# tick-mk-4_5.net
KiCad netlist of a schematic drawn in EAGLE
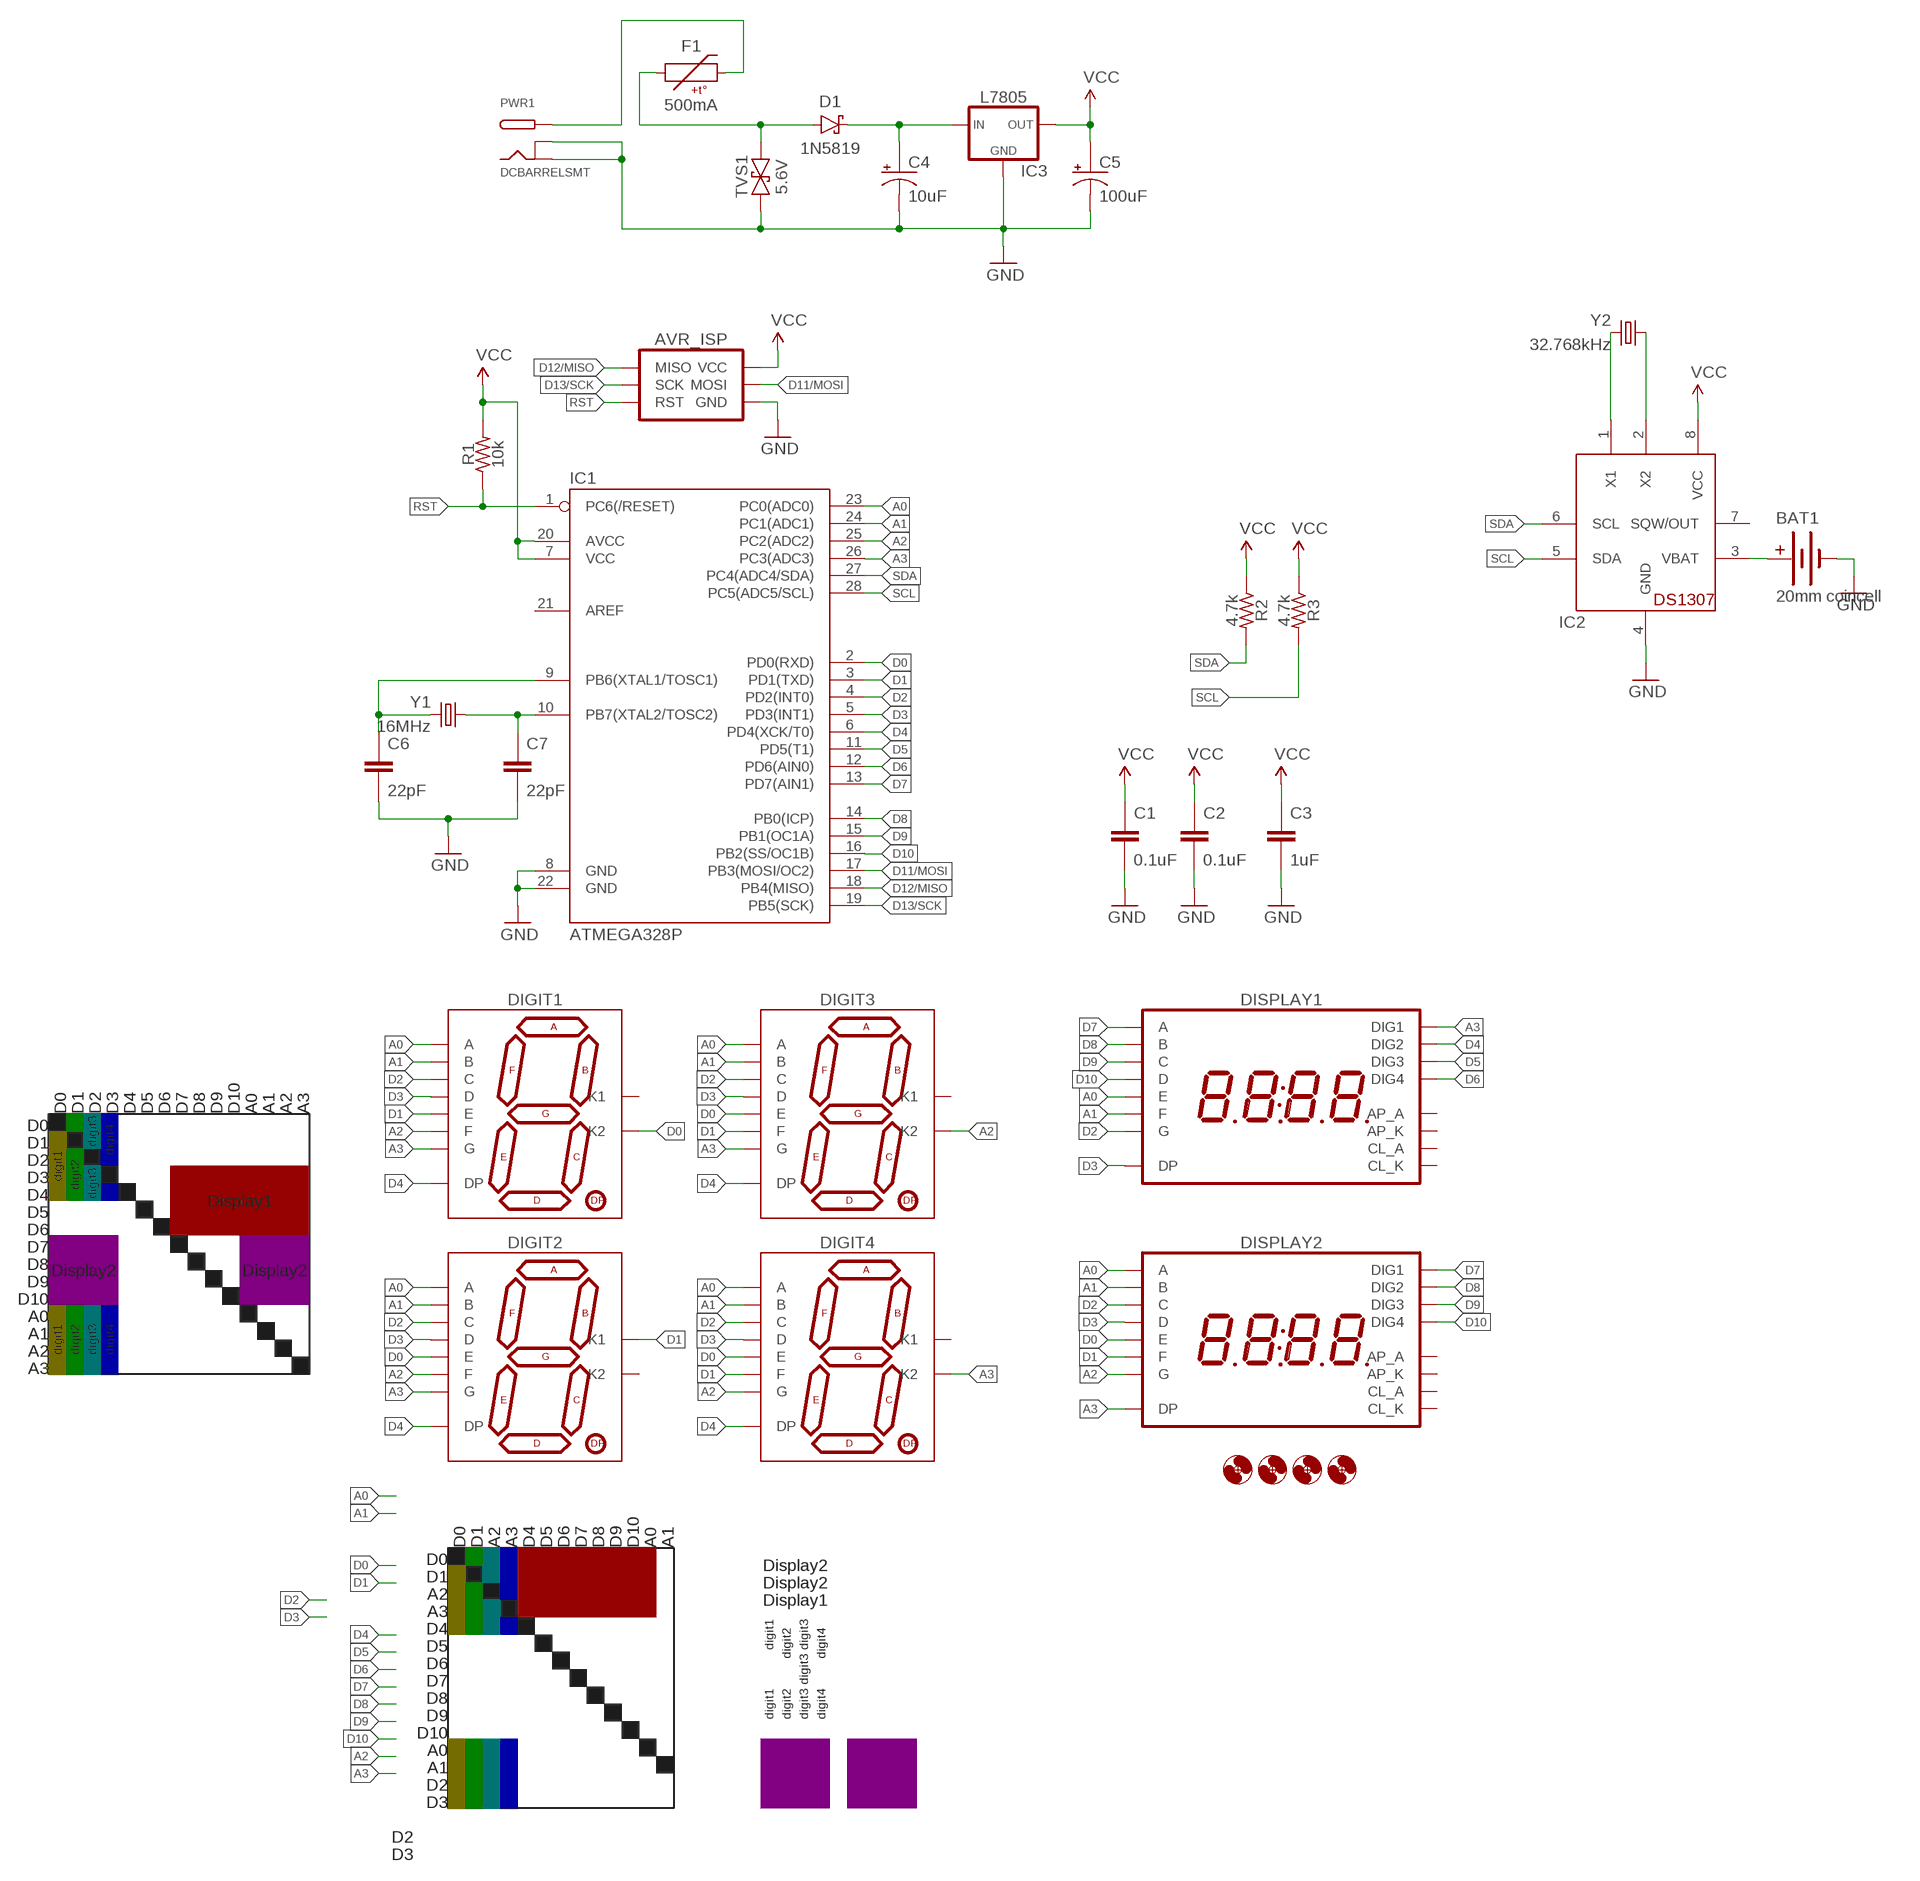
[diagram p0: schematic, sheet 1]

(export (version "E")
  (design (tool "Eeschema 10.0.6"))
  (components
    (comp (ref "AVR_ISP")
      (value "AVR_SPI_PRG_6PTH")
      (footprint "eagle-import:2X3")
      (libsource (lib "eagle-import") (part "AVR_SPI_PRG_6PTH"))
    )
    (comp (ref "BAT1")
      (value "20mm coincell")
      (footprint "eagle-import:BATTCON_20MM_MINE")
      (libsource (lib "eagle-import") (part "BATTERY20MMSMD-MINE"))
    )
    (comp (ref "C1")
      (value "0.1uF")
      (footprint "eagle-import:C025-024X044")
      (libsource (lib "eagle-import") (part "CAPACITOR-CERAMIC025-024X044"))
    )
    (comp (ref "C2")
      (value "0.1uF")
      (footprint "eagle-import:C025-024X044")
      (libsource (lib "eagle-import") (part "CAPACITOR-CERAMIC025-024X044"))
    )
    (comp (ref "C3")
      (value "1uF")
      (footprint "eagle-import:C025-024X044")
      (libsource (lib "eagle-import") (part "CAPACITOR-CERAMIC025-024X044"))
    )
    (comp (ref "C4")
      (value "10uF")
      (footprint "eagle-import:E2-5")
      (libsource (lib "eagle-import") (part "CAPACITOR-POLARIZEDE2-5"))
    )
    (comp (ref "C5")
      (value "100uF")
      (footprint "eagle-import:E2,5-6")
      (libsource (lib "eagle-import") (part "CAPACITOR-POLARIZEDE2.5-6"))
    )
    (comp (ref "C6")
      (value "22pF")
      (footprint "eagle-import:C025-024X044")
      (libsource (lib "eagle-import") (part "CAPACITOR-CERAMIC025-024X044"))
    )
    (comp (ref "C7")
      (value "22pF")
      (footprint "eagle-import:C025-024X044")
      (libsource (lib "eagle-import") (part "CAPACITOR-CERAMIC025-024X044"))
    )
    (comp (ref "D1")
      (value "1N5819")
      (footprint "eagle-import:DIODE-10.16MM")
      (libsource (lib "eagle-import") (part "DIODE-SCHOTTKYPTH-10.16MM"))
    )
    (comp (ref "DIGIT1")
      (value "7SEG_1DIGPTH-25.4MM-BARE")
      (footprint "eagle-import:7SEG_1DIG_25.4MM_NOSILK")
      (libsource (lib "eagle-import") (part "7SEG_1DIGPTH-25.4MM-BARE"))
    )
    (comp (ref "DIGIT2")
      (value "7SEG_1DIGPTH-25.4MM-BARE")
      (footprint "eagle-import:7SEG_1DIG_25.4MM_NOSILK")
      (libsource (lib "eagle-import") (part "7SEG_1DIGPTH-25.4MM-BARE"))
    )
    (comp (ref "DIGIT3")
      (value "7SEG_1DIGPTH-25.4MM-BARE")
      (footprint "eagle-import:7SEG_1DIG_25.4MM_NOSILK")
      (libsource (lib "eagle-import") (part "7SEG_1DIGPTH-25.4MM-BARE"))
    )
    (comp (ref "DIGIT4")
      (value "7SEG_1DIGPTH-25.4MM-BARE")
      (footprint "eagle-import:7SEG_1DIG_25.4MM_NOSILK")
      (libsource (lib "eagle-import") (part "7SEG_1DIGPTH-25.4MM-BARE"))
    )
    (comp (ref "DISPLAY1")
      (value "7SEG_4DIGIT_COLON_APOS")
      (footprint "eagle-import:7SEG_4DIG_10MM")
      (libsource (lib "eagle-import") (part "7SEG_4DIGIT_COLON_APOS"))
    )
    (comp (ref "DISPLAY2")
      (value "7SEG_4DIGIT_COLON_APOS")
      (footprint "eagle-import:7SEG_4DIG_10MM")
      (libsource (lib "eagle-import") (part "7SEG_4DIGIT_COLON_APOS"))
    )
    (comp (ref "F1")
      (value "500mA")
      (footprint "eagle-import:PTC-PTH-5.08MM")
      (libsource (lib "eagle-import") (part "PTCPTH-5.08MM"))
    )
    (comp (ref "H1")
      (value "HOLE#2")
      (footprint "eagle-import:HOLE-#2")
      (libsource (lib "eagle-import") (part "HOLE#2"))
    )
    (comp (ref "H2")
      (value "HOLE#2")
      (footprint "eagle-import:HOLE-#2")
      (libsource (lib "eagle-import") (part "HOLE#2"))
    )
    (comp (ref "H3")
      (value "HOLE#2")
      (footprint "eagle-import:HOLE-#2")
      (libsource (lib "eagle-import") (part "HOLE#2"))
    )
    (comp (ref "H4")
      (value "HOLE#2")
      (footprint "eagle-import:HOLE-#2")
      (libsource (lib "eagle-import") (part "HOLE#2"))
    )
    (comp (ref "IC1")
      (value "ATMEGA328P")
      (footprint "eagle-import:DIL28-3")
      (libsource (lib "eagle-import") (part "ATMEGA328P_PDIP"))
    )
    (comp (ref "IC2")
      (value "DS1307")
      (footprint "eagle-import:DIL08")
      (libsource (lib "eagle-import") (part "DS1307"))
    )
    (comp (ref "IC3")
      (value "L7805")
      (footprint "eagle-import:TO220-IGO-THERMPAD")
      (libsource (lib "eagle-import") (part "V_REG_78XXTO-220-THERMPAD"))
    )
    (comp (ref "PWR1")
      (value "DCBARRELSMT")
      (footprint "eagle-import:DCJACK_2MM_SMT")
      (libsource (lib "eagle-import") (part "DCBARRELSMT"))
    )
    (comp (ref "R1")
      (value "10k")
      (footprint "eagle-import:RESISTOR-AXIAL-PTH-7.62MM")
      (libsource (lib "eagle-import") (part "RESISTORPTH-AXIAL-7.62MM"))
    )
    (comp (ref "R2")
      (value "4.7k")
      (footprint "eagle-import:RESISTOR-AXIAL-PTH-7.62MM")
      (libsource (lib "eagle-import") (part "RESISTORPTH-AXIAL-7.62MM"))
    )
    (comp (ref "R3")
      (value "4.7k")
      (footprint "eagle-import:RESISTOR-AXIAL-PTH-7.62MM")
      (libsource (lib "eagle-import") (part "RESISTORPTH-AXIAL-7.62MM"))
    )
    (comp (ref "TVS1")
      (value "5.6V")
      (footprint "eagle-import:DO-41-TVS-BI-10.16MM")
      (libsource (lib "eagle-import") (part "TVSDO-41-10.16MM"))
    )
    (comp (ref "Y1")
      (value "16MHz")
      (footprint "eagle-import:HC49U-V")
      (libsource (lib "eagle-import") (part "CRYSTALHC49UV"))
    )
    (comp (ref "Y2")
      (value "32.768kHz")
      (footprint "eagle-import:TC26H")
      (libsource (lib "eagle-import") (part "CRYSTALTC26H"))
    )
  )
  (nets
    (net (code "1") (name "A0") (class "Default")
      (node (ref "DIGIT1") (pin "7") (pinfunction "A_7") (pintype "bidirectional"))
      (node (ref "DIGIT2") (pin "7") (pinfunction "A_7") (pintype "bidirectional"))
      (node (ref "DIGIT3") (pin "7") (pinfunction "A_7") (pintype "bidirectional"))
      (node (ref "DIGIT4") (pin "7") (pinfunction "A_7") (pintype "bidirectional"))
      (node (ref "DISPLAY1") (pin "5") (pinfunction "E_5") (pintype "passive"))
      (node (ref "DISPLAY2") (pin "14") (pinfunction "A_14") (pintype "passive"))
      (node (ref "IC1") (pin "23") (pinfunction "PC0(ADC0)_23") (pintype "bidirectional"))
    )
    (net (code "2") (name "A1") (class "Default")
      (node (ref "DIGIT1") (pin "6") (pinfunction "B_6") (pintype "bidirectional"))
      (node (ref "DIGIT2") (pin "6") (pinfunction "B_6") (pintype "bidirectional"))
      (node (ref "DIGIT3") (pin "6") (pinfunction "B_6") (pintype "bidirectional"))
      (node (ref "DIGIT4") (pin "6") (pinfunction "B_6") (pintype "bidirectional"))
      (node (ref "DISPLAY1") (pin "11") (pinfunction "F_11") (pintype "passive"))
      (node (ref "DISPLAY2") (pin "16") (pinfunction "B_16") (pintype "passive"))
      (node (ref "IC1") (pin "24") (pinfunction "PC1(ADC1)_24") (pintype "bidirectional"))
    )
    (net (code "3") (name "A2") (class "Default")
      (node (ref "DIGIT1") (pin "9") (pinfunction "F_9") (pintype "bidirectional"))
      (node (ref "DIGIT2") (pin "9") (pinfunction "F_9") (pintype "bidirectional"))
      (node (ref "DIGIT3") (pin "8") (pinfunction "K2_8") (pintype "bidirectional"))
      (node (ref "DIGIT4") (pin "10") (pinfunction "G_10") (pintype "bidirectional"))
      (node (ref "DISPLAY2") (pin "15") (pinfunction "G_15") (pintype "passive"))
      (node (ref "IC1") (pin "25") (pinfunction "PC2(ADC2)_25") (pintype "bidirectional"))
    )
    (net (code "4") (name "A3") (class "Default")
      (node (ref "DIGIT1") (pin "10") (pinfunction "G_10") (pintype "bidirectional"))
      (node (ref "DIGIT2") (pin "10") (pinfunction "G_10") (pintype "bidirectional"))
      (node (ref "DIGIT3") (pin "10") (pinfunction "G_10") (pintype "bidirectional"))
      (node (ref "DIGIT4") (pin "8") (pinfunction "K2_8") (pintype "bidirectional"))
      (node (ref "DISPLAY1") (pin "1") (pinfunction "DIG1_1") (pintype "passive"))
      (node (ref "DISPLAY2") (pin "7") (pinfunction "DP_7") (pintype "passive"))
      (node (ref "IC1") (pin "26") (pinfunction "PC3(ADC3)_26") (pintype "bidirectional"))
    )
    (net (code "5") (name "D0") (class "Default")
      (node (ref "DIGIT1") (pin "8") (pinfunction "K2_8") (pintype "bidirectional"))
      (node (ref "DIGIT2") (pin "1") (pinfunction "E_1") (pintype "bidirectional"))
      (node (ref "DIGIT3") (pin "1") (pinfunction "E_1") (pintype "bidirectional"))
      (node (ref "DIGIT4") (pin "1") (pinfunction "E_1") (pintype "bidirectional"))
      (node (ref "DISPLAY2") (pin "5") (pinfunction "E_5") (pintype "passive"))
      (node (ref "IC1") (pin "2") (pinfunction "PD0(RXD)_2") (pintype "bidirectional"))
    )
    (net (code "6") (name "D1") (class "Default")
      (node (ref "DIGIT1") (pin "1") (pinfunction "E_1") (pintype "bidirectional"))
      (node (ref "DIGIT2") (pin "3") (pinfunction "K1_3") (pintype "bidirectional"))
      (node (ref "DIGIT3") (pin "9") (pinfunction "F_9") (pintype "bidirectional"))
      (node (ref "DIGIT4") (pin "9") (pinfunction "F_9") (pintype "bidirectional"))
      (node (ref "DISPLAY2") (pin "11") (pinfunction "F_11") (pintype "passive"))
      (node (ref "IC1") (pin "3") (pinfunction "PD1(TXD)_3") (pintype "bidirectional"))
    )
    (net (code "7") (name "D2") (class "Default")
      (node (ref "DIGIT1") (pin "4") (pinfunction "C_4") (pintype "bidirectional"))
      (node (ref "DIGIT2") (pin "4") (pinfunction "C_4") (pintype "bidirectional"))
      (node (ref "DIGIT3") (pin "4") (pinfunction "C_4") (pintype "bidirectional"))
      (node (ref "DIGIT4") (pin "4") (pinfunction "C_4") (pintype "bidirectional"))
      (node (ref "DISPLAY1") (pin "15") (pinfunction "G_15") (pintype "passive"))
      (node (ref "DISPLAY2") (pin "13") (pinfunction "C_13") (pintype "passive"))
      (node (ref "IC1") (pin "4") (pinfunction "PD2(INT0)_4") (pintype "bidirectional"))
    )
    (net (code "8") (name "D3") (class "Default")
      (node (ref "DIGIT1") (pin "2") (pinfunction "D_2") (pintype "bidirectional"))
      (node (ref "DIGIT2") (pin "2") (pinfunction "D_2") (pintype "bidirectional"))
      (node (ref "DIGIT3") (pin "2") (pinfunction "D_2") (pintype "bidirectional"))
      (node (ref "DIGIT4") (pin "2") (pinfunction "D_2") (pintype "bidirectional"))
      (node (ref "DISPLAY1") (pin "7") (pinfunction "DP_7") (pintype "passive"))
      (node (ref "DISPLAY2") (pin "3") (pinfunction "D_3") (pintype "passive"))
      (node (ref "IC1") (pin "5") (pinfunction "PD3(INT1)_5") (pintype "bidirectional"))
    )
    (net (code "9") (name "D4") (class "Default")
      (node (ref "DIGIT1") (pin "5") (pinfunction "DP_5") (pintype "bidirectional"))
      (node (ref "DIGIT2") (pin "5") (pinfunction "DP_5") (pintype "bidirectional"))
      (node (ref "DIGIT3") (pin "5") (pinfunction "DP_5") (pintype "bidirectional"))
      (node (ref "DIGIT4") (pin "5") (pinfunction "DP_5") (pintype "bidirectional"))
      (node (ref "DISPLAY1") (pin "2") (pinfunction "DIG2_2") (pintype "passive"))
      (node (ref "IC1") (pin "6") (pinfunction "PD4(XCK/T0)_6") (pintype "bidirectional"))
    )
    (net (code "10") (name "D5") (class "Default")
      (node (ref "DISPLAY1") (pin "6") (pinfunction "DIG3_6") (pintype "passive"))
      (node (ref "IC1") (pin "11") (pinfunction "PD5(T1)_11") (pintype "bidirectional"))
    )
    (net (code "11") (name "D6") (class "Default")
      (node (ref "DISPLAY1") (pin "8") (pinfunction "DIG4_8") (pintype "passive"))
      (node (ref "IC1") (pin "12") (pinfunction "PD6(AIN0)_12") (pintype "bidirectional"))
    )
    (net (code "12") (name "D7") (class "Default")
      (node (ref "DISPLAY1") (pin "14") (pinfunction "A_14") (pintype "passive"))
      (node (ref "DISPLAY2") (pin "1") (pinfunction "DIG1_1") (pintype "passive"))
      (node (ref "IC1") (pin "13") (pinfunction "PD7(AIN1)_13") (pintype "bidirectional"))
    )
    (net (code "13") (name "D8") (class "Default")
      (node (ref "DISPLAY1") (pin "16") (pinfunction "B_16") (pintype "passive"))
      (node (ref "DISPLAY2") (pin "2") (pinfunction "DIG2_2") (pintype "passive"))
      (node (ref "IC1") (pin "14") (pinfunction "PB0(ICP)_14") (pintype "bidirectional"))
    )
    (net (code "14") (name "D9") (class "Default")
      (node (ref "DISPLAY1") (pin "13") (pinfunction "C_13") (pintype "passive"))
      (node (ref "DISPLAY2") (pin "6") (pinfunction "DIG3_6") (pintype "passive"))
      (node (ref "IC1") (pin "15") (pinfunction "PB1(OC1A)_15") (pintype "bidirectional"))
    )
    (net (code "15") (name "D10") (class "Default")
      (node (ref "DISPLAY1") (pin "3") (pinfunction "D_3") (pintype "passive"))
      (node (ref "DISPLAY2") (pin "8") (pinfunction "DIG4_8") (pintype "passive"))
      (node (ref "IC1") (pin "16") (pinfunction "PB2(SS/OC1B)_16") (pintype "bidirectional"))
    )
    (net (code "16") (name "D11{slash}MOSI") (class "Default")
      (node (ref "AVR_ISP") (pin "4") (pinfunction "MOSI_4") (pintype "passive"))
      (node (ref "IC1") (pin "17") (pinfunction "PB3(MOSI/OC2)_17") (pintype "bidirectional"))
    )
    (net (code "17") (name "D12{slash}MISO") (class "Default")
      (node (ref "AVR_ISP") (pin "1") (pinfunction "MISO_1") (pintype "passive"))
      (node (ref "IC1") (pin "18") (pinfunction "PB4(MISO)_18") (pintype "bidirectional"))
    )
    (net (code "18") (name "D13{slash}SCK") (class "Default")
      (node (ref "AVR_ISP") (pin "3") (pinfunction "SCK_3") (pintype "passive"))
      (node (ref "IC1") (pin "19") (pinfunction "PB5(SCK)_19") (pintype "bidirectional"))
    )
    (net (code "19") (name "GND") (class "Default")
      (node (ref "AVR_ISP") (pin "6") (pinfunction "GND_6") (pintype "passive"))
      (node (ref "BAT1") (pin "BOTTOM") (pinfunction "-_BOTTOM") (pintype "power_in"))
      (node (ref "C1") (pin "2") (pinfunction "2_2") (pintype "passive"))
      (node (ref "C2") (pin "2") (pinfunction "2_2") (pintype "passive"))
      (node (ref "C3") (pin "2") (pinfunction "2_2") (pintype "passive"))
      (node (ref "C4") (pin "-") (pinfunction "-_-") (pintype "passive"))
      (node (ref "C5") (pin "-") (pinfunction "-_-") (pintype "passive"))
      (node (ref "C6") (pin "2") (pinfunction "2_2") (pintype "passive"))
      (node (ref "C7") (pin "2") (pinfunction "2_2") (pintype "passive"))
      (node (ref "IC1") (pin "22") (pinfunction "GND_22") (pintype "bidirectional"))
      (node (ref "IC1") (pin "8") (pinfunction "GND_8") (pintype "bidirectional"))
      (node (ref "IC2") (pin "4") (pinfunction "GND_4") (pintype "power_in"))
      (node (ref "IC3") (pin "4") (pinfunction "GND_4") (pintype "bidirectional"))
      (node (ref "IC3") (pin "GND") (pinfunction "GND_GND") (pintype "bidirectional"))
      (node (ref "PWR1") (pin "BRK") (pinfunction "BRK_BRK") (pintype "bidirectional"))
      (node (ref "PWR1") (pin "GND") (pinfunction "GND_GND") (pintype "bidirectional"))
      (node (ref "TVS1") (pin "P$1") (pinfunction "1_P$1") (pintype "passive"))
    )
    (net (code "20") (name "Net-(C4-Pad+)") (class "Default")
      (node (ref "C4") (pin "+") (pinfunction "+_+") (pintype "passive"))
      (node (ref "D1") (pin "C") (pinfunction "C_C") (pintype "passive"))
      (node (ref "IC3") (pin "IN") (pinfunction "IN_IN") (pintype "bidirectional"))
    )
    (net (code "21") (name "Net-(F1-1)") (class "Default")
      (node (ref "D1") (pin "A") (pinfunction "A_A") (pintype "passive"))
      (node (ref "F1") (pin "P$1") (pinfunction "1_P$1") (pintype "passive"))
      (node (ref "TVS1") (pin "P$2") (pinfunction "2_P$2") (pintype "passive"))
    )
    (net (code "22") (name "Net-(F1-2)") (class "Default")
      (node (ref "F1") (pin "P$2") (pinfunction "2_P$2") (pintype "passive"))
      (node (ref "PWR1") (pin "PWR@1") (pinfunction "PWR_PWR@1") (pintype "bidirectional"))
      (node (ref "PWR1") (pin "PWR@2") (pinfunction "PWR_PWR@2") (pintype "bidirectional"))
    )
    (net (code "23") (name "Net-(IC1-PB6(XTAL1{slash}TOSC1))") (class "Default")
      (node (ref "C6") (pin "1") (pinfunction "1_1") (pintype "passive"))
      (node (ref "IC1") (pin "9") (pinfunction "PB6(XTAL1/TOSC1)_9") (pintype "bidirectional"))
      (node (ref "Y1") (pin "2") (pinfunction "2_2") (pintype "passive"))
    )
    (net (code "24") (name "Net-(IC1-PB7(XTAL2{slash}TOSC2))") (class "Default")
      (node (ref "C7") (pin "1") (pinfunction "1_1") (pintype "passive"))
      (node (ref "IC1") (pin "10") (pinfunction "PB7(XTAL2/TOSC2)_10") (pintype "bidirectional"))
      (node (ref "Y1") (pin "1") (pinfunction "1_1") (pintype "passive"))
    )
    (net (code "25") (name "Net-(IC2-VBAT)") (class "Default")
      (node (ref "BAT1") (pin "TOP@1") (pinfunction "+_TOP@1") (pintype "power_in"))
      (node (ref "BAT1") (pin "TOP@2") (pinfunction "+_TOP@2") (pintype "power_in"))
      (node (ref "IC2") (pin "3") (pinfunction "VBAT_3") (pintype "power_in"))
    )
    (net (code "26") (name "Net-(IC2-X1)") (class "Default")
      (node (ref "IC2") (pin "1") (pinfunction "X1_1") (pintype "passive"))
      (node (ref "Y2") (pin "2") (pinfunction "2_2") (pintype "passive"))
    )
    (net (code "27") (name "Net-(IC2-X2)") (class "Default")
      (node (ref "IC2") (pin "2") (pinfunction "X2_2") (pintype "passive"))
      (node (ref "Y2") (pin "1") (pinfunction "1_1") (pintype "passive"))
    )
    (net (code "28") (name "RST") (class "Default")
      (node (ref "AVR_ISP") (pin "5") (pinfunction "RST_5") (pintype "passive"))
      (node (ref "IC1") (pin "1") (pinfunction "PC6(/RESET)_1") (pintype "bidirectional"))
      (node (ref "R1") (pin "P$1") (pinfunction "1_P$1") (pintype "passive"))
    )
    (net (code "29") (name "SCL") (class "Default")
      (node (ref "IC1") (pin "28") (pinfunction "PC5(ADC5/SCL)_28") (pintype "bidirectional"))
      (node (ref "IC2") (pin "5") (pinfunction "SDA_5") (pintype "bidirectional"))
      (node (ref "R3") (pin "P$2") (pinfunction "2_P$2") (pintype "passive"))
    )
    (net (code "30") (name "SDA") (class "Default")
      (node (ref "IC1") (pin "27") (pinfunction "PC4(ADC4/SDA)_27") (pintype "bidirectional"))
      (node (ref "IC2") (pin "6") (pinfunction "SCL_6") (pintype "bidirectional"))
      (node (ref "R2") (pin "P$2") (pinfunction "2_P$2") (pintype "passive"))
    )
    (net (code "31") (name "VCC") (class "Default")
      (node (ref "AVR_ISP") (pin "2") (pinfunction "VCC_2") (pintype "passive"))
      (node (ref "C1") (pin "1") (pinfunction "1_1") (pintype "passive"))
      (node (ref "C2") (pin "1") (pinfunction "1_1") (pintype "passive"))
      (node (ref "C3") (pin "1") (pinfunction "1_1") (pintype "passive"))
      (node (ref "C5") (pin "+") (pinfunction "+_+") (pintype "passive"))
      (node (ref "IC1") (pin "20") (pinfunction "AVCC_20") (pintype "bidirectional"))
      (node (ref "IC1") (pin "7") (pinfunction "VCC_7") (pintype "bidirectional"))
      (node (ref "IC2") (pin "8") (pinfunction "VCC_8") (pintype "power_in"))
      (node (ref "IC3") (pin "OUT") (pinfunction "OUT_OUT") (pintype "bidirectional"))
      (node (ref "R1") (pin "P$2") (pinfunction "2_P$2") (pintype "passive"))
      (node (ref "R2") (pin "P$1") (pinfunction "1_P$1") (pintype "passive"))
      (node (ref "R3") (pin "P$1") (pinfunction "1_P$1") (pintype "passive"))
    )
    (net (code "32") (name "unconnected-(DIGIT1-K1-Pad3)") (class "Default")
      (node (ref "DIGIT1") (pin "3") (pinfunction "K1_3") (pintype "bidirectional"))
    )
    (net (code "33") (name "unconnected-(DIGIT2-K2-Pad8)") (class "Default")
      (node (ref "DIGIT2") (pin "8") (pinfunction "K2_8") (pintype "bidirectional"))
    )
    (net (code "34") (name "unconnected-(DIGIT3-K1-Pad3)") (class "Default")
      (node (ref "DIGIT3") (pin "3") (pinfunction "K1_3") (pintype "bidirectional"))
    )
    (net (code "35") (name "unconnected-(DIGIT4-K1-Pad3)") (class "Default")
      (node (ref "DIGIT4") (pin "3") (pinfunction "K1_3") (pintype "bidirectional"))
    )
    (net (code "36") (name "unconnected-(DISPLAY1-AP_A-Pad10)") (class "Default")
      (node (ref "DISPLAY1") (pin "10") (pinfunction "AP_A_10") (pintype "bidirectional"))
    )
    (net (code "37") (name "unconnected-(DISPLAY1-AP_K-Pad9)") (class "Default")
      (node (ref "DISPLAY1") (pin "9") (pinfunction "AP_K_9") (pintype "bidirectional"))
    )
    (net (code "38") (name "unconnected-(DISPLAY1-CL_A-Pad4)") (class "Default")
      (node (ref "DISPLAY1") (pin "4") (pinfunction "CL_A_4") (pintype "passive"))
    )
    (net (code "39") (name "unconnected-(DISPLAY1-CL_K-Pad12)") (class "Default")
      (node (ref "DISPLAY1") (pin "12") (pinfunction "CL_K_12") (pintype "passive"))
    )
    (net (code "40") (name "unconnected-(DISPLAY2-AP_A-Pad10)") (class "Default")
      (node (ref "DISPLAY2") (pin "10") (pinfunction "AP_A_10") (pintype "bidirectional"))
    )
    (net (code "41") (name "unconnected-(DISPLAY2-AP_K-Pad9)") (class "Default")
      (node (ref "DISPLAY2") (pin "9") (pinfunction "AP_K_9") (pintype "bidirectional"))
    )
    (net (code "42") (name "unconnected-(DISPLAY2-CL_A-Pad4)") (class "Default")
      (node (ref "DISPLAY2") (pin "4") (pinfunction "CL_A_4") (pintype "passive"))
    )
    (net (code "43") (name "unconnected-(DISPLAY2-CL_K-Pad12)") (class "Default")
      (node (ref "DISPLAY2") (pin "12") (pinfunction "CL_K_12") (pintype "passive"))
    )
    (net (code "44") (name "unconnected-(IC1-AREF-Pad21)") (class "Default")
      (node (ref "IC1") (pin "21") (pinfunction "AREF_21") (pintype "bidirectional"))
    )
    (net (code "45") (name "unconnected-(IC2-SQW{slash}OUT-Pad7)") (class "Default")
      (node (ref "IC2") (pin "7") (pinfunction "SQW/OUT_7") (pintype "bidirectional"))
    )
  )
)
